# PC1-ISA.net
KiCad netlist of a schematic drawn in EAGLE
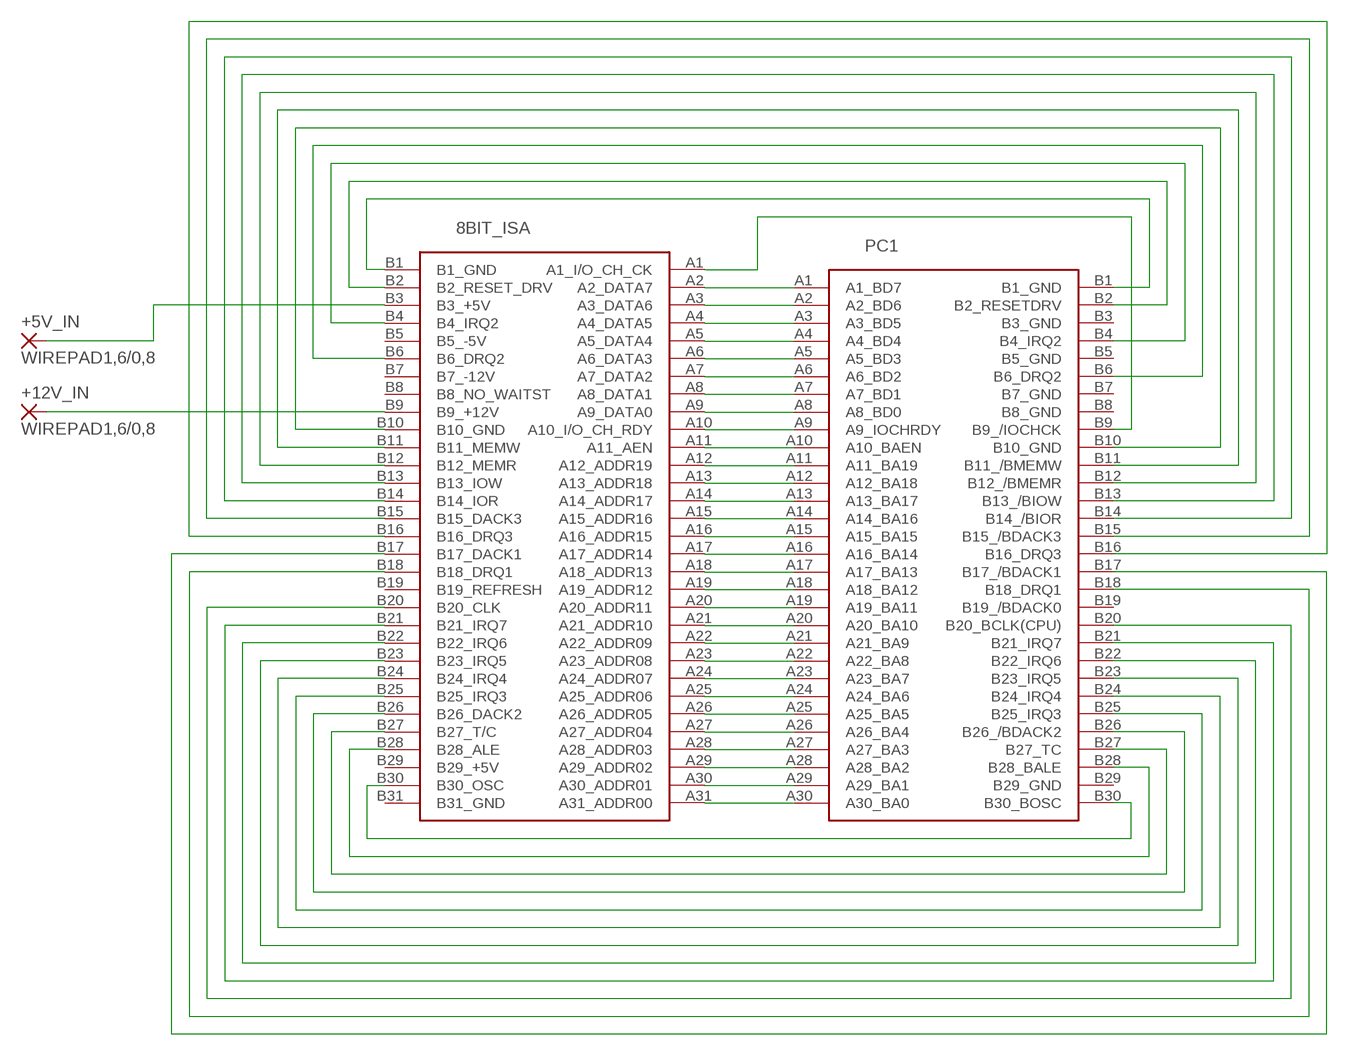
[diagram p0: schematic, sheet 1]

(export (version "E")
  (design (tool "Eeschema 10.0.6"))
  (components
    (comp (ref "+5V_IN")
      (value "WIREPAD1,6/0,8")
      (footprint "eagle-import:1,6_0,8")
      (libsource (lib "eagle-import") (part "WIREPAD1,6/0,8"))
    )
    (comp (ref "+12V_IN")
      (value "WIREPAD1,6/0,8")
      (footprint "eagle-import:1,6_0,8")
      (libsource (lib "eagle-import") (part "WIREPAD1,6/0,8"))
    )
    (comp (ref "8BIT_ISA")
      (value "CARDEDGE_FEMALE_62PINS_8BITISA_STRAIGHT")
      (footprint "eagle-import:CARDEDGE_FEMALE_62PINS_8BITISA_STRAIGHT")
      (libsource (lib "eagle-import") (part "CARDEDGE_FEMALE_62PINS_8BITISA_STRAIGHT"))
    )
    (comp (ref "PC1")
      (value "CARDEDGE_FEMALE_60PINS_PC1_ANGLEDLEFT")
      (footprint "eagle-import:CARDEDGE_FEMALE_60PINS_PC1_ANGLEDLEFT")
      (libsource (lib "eagle-import") (part "CARDEDGE_FEMALE_60PINS_PC1_ANGLEDLEFT"))
    )
  )
  (nets
    (net (code "1") (name "Net-(+5V_IN-P)") (class "Default")
      (node (ref "+5V_IN") (pin "1") (pinfunction "P_1") (pintype "passive"))
      (node (ref "8BIT_ISA") (pin "B3") (pinfunction "B3_+5V_B3") (pintype "bidirectional"))
    )
    (net (code "2") (name "Net-(+12V_IN-P)") (class "Default")
      (node (ref "+12V_IN") (pin "1") (pinfunction "P_1") (pintype "passive"))
      (node (ref "8BIT_ISA") (pin "B9") (pinfunction "B9_+12V_B9") (pintype "bidirectional"))
    )
    (net (code "3") (name "Net-(8BIT_ISA-A1_I{slash}O_CH_CK)") (class "Default")
      (node (ref "8BIT_ISA") (pin "A1") (pinfunction "A1_I/O_CH_CK_A1") (pintype "bidirectional"))
      (node (ref "PC1") (pin "B9") (pinfunction "B9_/IOCHCK_B9") (pintype "bidirectional"))
    )
    (net (code "4") (name "Net-(8BIT_ISA-A2_DATA7)") (class "Default")
      (node (ref "8BIT_ISA") (pin "A2") (pinfunction "A2_DATA7_A2") (pintype "bidirectional"))
      (node (ref "PC1") (pin "A1") (pinfunction "A1_BD7_A1") (pintype "bidirectional"))
    )
    (net (code "5") (name "Net-(8BIT_ISA-A3_DATA6)") (class "Default")
      (node (ref "8BIT_ISA") (pin "A3") (pinfunction "A3_DATA6_A3") (pintype "bidirectional"))
      (node (ref "PC1") (pin "A2") (pinfunction "A2_BD6_A2") (pintype "bidirectional"))
    )
    (net (code "6") (name "Net-(8BIT_ISA-A4_DATA5)") (class "Default")
      (node (ref "8BIT_ISA") (pin "A4") (pinfunction "A4_DATA5_A4") (pintype "bidirectional"))
      (node (ref "PC1") (pin "A3") (pinfunction "A3_BD5_A3") (pintype "bidirectional"))
    )
    (net (code "7") (name "Net-(8BIT_ISA-A5_DATA4)") (class "Default")
      (node (ref "8BIT_ISA") (pin "A5") (pinfunction "A5_DATA4_A5") (pintype "bidirectional"))
      (node (ref "PC1") (pin "A4") (pinfunction "A4_BD4_A4") (pintype "bidirectional"))
    )
    (net (code "8") (name "Net-(8BIT_ISA-A6_DATA3)") (class "Default")
      (node (ref "8BIT_ISA") (pin "A6") (pinfunction "A6_DATA3_A6") (pintype "bidirectional"))
      (node (ref "PC1") (pin "A5") (pinfunction "A5_BD3_A5") (pintype "bidirectional"))
    )
    (net (code "9") (name "Net-(8BIT_ISA-A7_DATA2)") (class "Default")
      (node (ref "8BIT_ISA") (pin "A7") (pinfunction "A7_DATA2_A7") (pintype "bidirectional"))
      (node (ref "PC1") (pin "A6") (pinfunction "A6_BD2_A6") (pintype "bidirectional"))
    )
    (net (code "10") (name "Net-(8BIT_ISA-A8_DATA1)") (class "Default")
      (node (ref "8BIT_ISA") (pin "A8") (pinfunction "A8_DATA1_A8") (pintype "bidirectional"))
      (node (ref "PC1") (pin "A7") (pinfunction "A7_BD1_A7") (pintype "bidirectional"))
    )
    (net (code "11") (name "Net-(8BIT_ISA-A9_DATA0)") (class "Default")
      (node (ref "8BIT_ISA") (pin "A9") (pinfunction "A9_DATA0_A9") (pintype "bidirectional"))
      (node (ref "PC1") (pin "A8") (pinfunction "A8_BD0_A8") (pintype "bidirectional"))
    )
    (net (code "12") (name "Net-(8BIT_ISA-A10_I{slash}O_CH_RDY)") (class "Default")
      (node (ref "8BIT_ISA") (pin "A10") (pinfunction "A10_I/O_CH_RDY_A10") (pintype "bidirectional"))
      (node (ref "PC1") (pin "A9") (pinfunction "A9_IOCHRDY_A9") (pintype "bidirectional"))
    )
    (net (code "13") (name "Net-(8BIT_ISA-A11_AEN)") (class "Default")
      (node (ref "8BIT_ISA") (pin "A11") (pinfunction "A11_AEN_A11") (pintype "bidirectional"))
      (node (ref "PC1") (pin "A10") (pinfunction "A10_BAEN_A10") (pintype "bidirectional"))
    )
    (net (code "14") (name "Net-(8BIT_ISA-A12_ADDR19)") (class "Default")
      (node (ref "8BIT_ISA") (pin "A12") (pinfunction "A12_ADDR19_A12") (pintype "bidirectional"))
      (node (ref "PC1") (pin "A11") (pinfunction "A11_BA19_A11") (pintype "bidirectional"))
    )
    (net (code "15") (name "Net-(8BIT_ISA-A13_ADDR18)") (class "Default")
      (node (ref "8BIT_ISA") (pin "A13") (pinfunction "A13_ADDR18_A13") (pintype "bidirectional"))
      (node (ref "PC1") (pin "A12") (pinfunction "A12_BA18_A12") (pintype "bidirectional"))
    )
    (net (code "16") (name "Net-(8BIT_ISA-A14_ADDR17)") (class "Default")
      (node (ref "8BIT_ISA") (pin "A14") (pinfunction "A14_ADDR17_A14") (pintype "bidirectional"))
      (node (ref "PC1") (pin "A13") (pinfunction "A13_BA17_A13") (pintype "bidirectional"))
    )
    (net (code "17") (name "Net-(8BIT_ISA-A15_ADDR16)") (class "Default")
      (node (ref "8BIT_ISA") (pin "A15") (pinfunction "A15_ADDR16_A15") (pintype "bidirectional"))
      (node (ref "PC1") (pin "A14") (pinfunction "A14_BA16_A14") (pintype "bidirectional"))
    )
    (net (code "18") (name "Net-(8BIT_ISA-A16_ADDR15)") (class "Default")
      (node (ref "8BIT_ISA") (pin "A16") (pinfunction "A16_ADDR15_A16") (pintype "bidirectional"))
      (node (ref "PC1") (pin "A15") (pinfunction "A15_BA15_A15") (pintype "bidirectional"))
    )
    (net (code "19") (name "Net-(8BIT_ISA-A17_ADDR14)") (class "Default")
      (node (ref "8BIT_ISA") (pin "A17") (pinfunction "A17_ADDR14_A17") (pintype "bidirectional"))
      (node (ref "PC1") (pin "A16") (pinfunction "A16_BA14_A16") (pintype "bidirectional"))
    )
    (net (code "20") (name "Net-(8BIT_ISA-A18_ADDR13)") (class "Default")
      (node (ref "8BIT_ISA") (pin "A18") (pinfunction "A18_ADDR13_A18") (pintype "bidirectional"))
      (node (ref "PC1") (pin "A17") (pinfunction "A17_BA13_A17") (pintype "bidirectional"))
    )
    (net (code "21") (name "Net-(8BIT_ISA-A19_ADDR12)") (class "Default")
      (node (ref "8BIT_ISA") (pin "A19") (pinfunction "A19_ADDR12_A19") (pintype "bidirectional"))
      (node (ref "PC1") (pin "A18") (pinfunction "A18_BA12_A18") (pintype "bidirectional"))
    )
    (net (code "22") (name "Net-(8BIT_ISA-A20_ADDR11)") (class "Default")
      (node (ref "8BIT_ISA") (pin "A20") (pinfunction "A20_ADDR11_A20") (pintype "bidirectional"))
      (node (ref "PC1") (pin "A19") (pinfunction "A19_BA11_A19") (pintype "bidirectional"))
    )
    (net (code "23") (name "Net-(8BIT_ISA-A21_ADDR10)") (class "Default")
      (node (ref "8BIT_ISA") (pin "A21") (pinfunction "A21_ADDR10_A21") (pintype "bidirectional"))
      (node (ref "PC1") (pin "A20") (pinfunction "A20_BA10_A20") (pintype "bidirectional"))
    )
    (net (code "24") (name "Net-(8BIT_ISA-A22_ADDR09)") (class "Default")
      (node (ref "8BIT_ISA") (pin "A22") (pinfunction "A22_ADDR09_A22") (pintype "bidirectional"))
      (node (ref "PC1") (pin "A21") (pinfunction "A21_BA9_A21") (pintype "bidirectional"))
    )
    (net (code "25") (name "Net-(8BIT_ISA-A23_ADDR08)") (class "Default")
      (node (ref "8BIT_ISA") (pin "A23") (pinfunction "A23_ADDR08_A23") (pintype "bidirectional"))
      (node (ref "PC1") (pin "A22") (pinfunction "A22_BA8_A22") (pintype "bidirectional"))
    )
    (net (code "26") (name "Net-(8BIT_ISA-A24_ADDR07)") (class "Default")
      (node (ref "8BIT_ISA") (pin "A24") (pinfunction "A24_ADDR07_A24") (pintype "bidirectional"))
      (node (ref "PC1") (pin "A23") (pinfunction "A23_BA7_A23") (pintype "bidirectional"))
    )
    (net (code "27") (name "Net-(8BIT_ISA-A25_ADDR06)") (class "Default")
      (node (ref "8BIT_ISA") (pin "A25") (pinfunction "A25_ADDR06_A25") (pintype "bidirectional"))
      (node (ref "PC1") (pin "A24") (pinfunction "A24_BA6_A24") (pintype "bidirectional"))
    )
    (net (code "28") (name "Net-(8BIT_ISA-A26_ADDR05)") (class "Default")
      (node (ref "8BIT_ISA") (pin "A26") (pinfunction "A26_ADDR05_A26") (pintype "bidirectional"))
      (node (ref "PC1") (pin "A25") (pinfunction "A25_BA5_A25") (pintype "bidirectional"))
    )
    (net (code "29") (name "Net-(8BIT_ISA-A27_ADDR04)") (class "Default")
      (node (ref "8BIT_ISA") (pin "A27") (pinfunction "A27_ADDR04_A27") (pintype "bidirectional"))
      (node (ref "PC1") (pin "A26") (pinfunction "A26_BA4_A26") (pintype "bidirectional"))
    )
    (net (code "30") (name "Net-(8BIT_ISA-A28_ADDR03)") (class "Default")
      (node (ref "8BIT_ISA") (pin "A28") (pinfunction "A28_ADDR03_A28") (pintype "bidirectional"))
      (node (ref "PC1") (pin "A27") (pinfunction "A27_BA3_A27") (pintype "bidirectional"))
    )
    (net (code "31") (name "Net-(8BIT_ISA-A29_ADDR02)") (class "Default")
      (node (ref "8BIT_ISA") (pin "A29") (pinfunction "A29_ADDR02_A29") (pintype "bidirectional"))
      (node (ref "PC1") (pin "A28") (pinfunction "A28_BA2_A28") (pintype "bidirectional"))
    )
    (net (code "32") (name "Net-(8BIT_ISA-A30_ADDR01)") (class "Default")
      (node (ref "8BIT_ISA") (pin "A30") (pinfunction "A30_ADDR01_A30") (pintype "bidirectional"))
      (node (ref "PC1") (pin "A29") (pinfunction "A29_BA1_A29") (pintype "bidirectional"))
    )
    (net (code "33") (name "Net-(8BIT_ISA-A31_ADDR00)") (class "Default")
      (node (ref "8BIT_ISA") (pin "A31") (pinfunction "A31_ADDR00_A31") (pintype "bidirectional"))
      (node (ref "PC1") (pin "A30") (pinfunction "A30_BA0_A30") (pintype "bidirectional"))
    )
    (net (code "34") (name "Net-(8BIT_ISA-B1_GND)") (class "Default")
      (node (ref "8BIT_ISA") (pin "B1") (pinfunction "B1_GND_B1") (pintype "bidirectional"))
      (node (ref "PC1") (pin "B1") (pinfunction "B1_GND_B1") (pintype "bidirectional"))
    )
    (net (code "35") (name "Net-(8BIT_ISA-B2_RESET_DRV)") (class "Default")
      (node (ref "8BIT_ISA") (pin "B2") (pinfunction "B2_RESET_DRV_B2") (pintype "bidirectional"))
      (node (ref "PC1") (pin "B2") (pinfunction "B2_RESETDRV_B2") (pintype "bidirectional"))
    )
    (net (code "36") (name "Net-(8BIT_ISA-B4_IRQ2)") (class "Default")
      (node (ref "8BIT_ISA") (pin "B4") (pinfunction "B4_IRQ2_B4") (pintype "bidirectional"))
      (node (ref "PC1") (pin "B4") (pinfunction "B4_IRQ2_B4") (pintype "bidirectional"))
    )
    (net (code "37") (name "Net-(8BIT_ISA-B6_DRQ2)") (class "Default")
      (node (ref "8BIT_ISA") (pin "B6") (pinfunction "B6_DRQ2_B6") (pintype "bidirectional"))
      (node (ref "PC1") (pin "B6") (pinfunction "B6_DRQ2_B6") (pintype "bidirectional"))
    )
    (net (code "38") (name "Net-(8BIT_ISA-B10_GND)") (class "Default")
      (node (ref "8BIT_ISA") (pin "B10") (pinfunction "B10_GND_B10") (pintype "bidirectional"))
      (node (ref "PC1") (pin "B10") (pinfunction "B10_GND_B10") (pintype "bidirectional"))
    )
    (net (code "39") (name "Net-(8BIT_ISA-B11_MEMW)") (class "Default")
      (node (ref "8BIT_ISA") (pin "B11") (pinfunction "B11_MEMW_B11") (pintype "bidirectional"))
      (node (ref "PC1") (pin "B11") (pinfunction "B11_/BMEMW_B11") (pintype "bidirectional"))
    )
    (net (code "40") (name "Net-(8BIT_ISA-B12_MEMR)") (class "Default")
      (node (ref "8BIT_ISA") (pin "B12") (pinfunction "B12_MEMR_B12") (pintype "bidirectional"))
      (node (ref "PC1") (pin "B12") (pinfunction "B12_/BMEMR_B12") (pintype "bidirectional"))
    )
    (net (code "41") (name "Net-(8BIT_ISA-B13_IOW)") (class "Default")
      (node (ref "8BIT_ISA") (pin "B13") (pinfunction "B13_IOW_B13") (pintype "bidirectional"))
      (node (ref "PC1") (pin "B13") (pinfunction "B13_/BIOW_B13") (pintype "bidirectional"))
    )
    (net (code "42") (name "Net-(8BIT_ISA-B14_IOR)") (class "Default")
      (node (ref "8BIT_ISA") (pin "B14") (pinfunction "B14_IOR_B14") (pintype "bidirectional"))
      (node (ref "PC1") (pin "B14") (pinfunction "B14_/BIOR_B14") (pintype "bidirectional"))
    )
    (net (code "43") (name "Net-(8BIT_ISA-B15_DACK3)") (class "Default")
      (node (ref "8BIT_ISA") (pin "B15") (pinfunction "B15_DACK3_B15") (pintype "bidirectional"))
      (node (ref "PC1") (pin "B15") (pinfunction "B15_/BDACK3_B15") (pintype "bidirectional"))
    )
    (net (code "44") (name "Net-(8BIT_ISA-B16_DRQ3)") (class "Default")
      (node (ref "8BIT_ISA") (pin "B16") (pinfunction "B16_DRQ3_B16") (pintype "bidirectional"))
      (node (ref "PC1") (pin "B16") (pinfunction "B16_DRQ3_B16") (pintype "bidirectional"))
    )
    (net (code "45") (name "Net-(8BIT_ISA-B17_DACK1)") (class "Default")
      (node (ref "8BIT_ISA") (pin "B17") (pinfunction "B17_DACK1_B17") (pintype "bidirectional"))
      (node (ref "PC1") (pin "B17") (pinfunction "B17_/BDACK1_B17") (pintype "bidirectional"))
    )
    (net (code "46") (name "Net-(8BIT_ISA-B18_DRQ1)") (class "Default")
      (node (ref "8BIT_ISA") (pin "B18") (pinfunction "B18_DRQ1_B18") (pintype "bidirectional"))
      (node (ref "PC1") (pin "B18") (pinfunction "B18_DRQ1_B18") (pintype "bidirectional"))
    )
    (net (code "47") (name "Net-(8BIT_ISA-B20_CLK)") (class "Default")
      (node (ref "8BIT_ISA") (pin "B20") (pinfunction "B20_CLK_B20") (pintype "bidirectional"))
      (node (ref "PC1") (pin "B20") (pinfunction "B20_BCLK(CPU)_B20") (pintype "bidirectional"))
    )
    (net (code "48") (name "Net-(8BIT_ISA-B21_IRQ7)") (class "Default")
      (node (ref "8BIT_ISA") (pin "B21") (pinfunction "B21_IRQ7_B21") (pintype "bidirectional"))
      (node (ref "PC1") (pin "B21") (pinfunction "B21_IRQ7_B21") (pintype "bidirectional"))
    )
    (net (code "49") (name "Net-(8BIT_ISA-B22_IRQ6)") (class "Default")
      (node (ref "8BIT_ISA") (pin "B22") (pinfunction "B22_IRQ6_B22") (pintype "bidirectional"))
      (node (ref "PC1") (pin "B22") (pinfunction "B22_IRQ6_B22") (pintype "bidirectional"))
    )
    (net (code "50") (name "Net-(8BIT_ISA-B23_IRQ5)") (class "Default")
      (node (ref "8BIT_ISA") (pin "B23") (pinfunction "B23_IRQ5_B23") (pintype "bidirectional"))
      (node (ref "PC1") (pin "B23") (pinfunction "B23_IRQ5_B23") (pintype "bidirectional"))
    )
    (net (code "51") (name "Net-(8BIT_ISA-B24_IRQ4)") (class "Default")
      (node (ref "8BIT_ISA") (pin "B24") (pinfunction "B24_IRQ4_B24") (pintype "bidirectional"))
      (node (ref "PC1") (pin "B24") (pinfunction "B24_IRQ4_B24") (pintype "bidirectional"))
    )
    (net (code "52") (name "Net-(8BIT_ISA-B25_IRQ3)") (class "Default")
      (node (ref "8BIT_ISA") (pin "B25") (pinfunction "B25_IRQ3_B25") (pintype "bidirectional"))
      (node (ref "PC1") (pin "B25") (pinfunction "B25_IRQ3_B25") (pintype "bidirectional"))
    )
    (net (code "53") (name "Net-(8BIT_ISA-B26_DACK2)") (class "Default")
      (node (ref "8BIT_ISA") (pin "B26") (pinfunction "B26_DACK2_B26") (pintype "bidirectional"))
      (node (ref "PC1") (pin "B26") (pinfunction "B26_/BDACK2_B26") (pintype "bidirectional"))
    )
    (net (code "54") (name "Net-(8BIT_ISA-B27_T{slash}C)") (class "Default")
      (node (ref "8BIT_ISA") (pin "B27") (pinfunction "B27_T/C_B27") (pintype "bidirectional"))
      (node (ref "PC1") (pin "B27") (pinfunction "B27_TC_B27") (pintype "bidirectional"))
    )
    (net (code "55") (name "Net-(8BIT_ISA-B28_ALE)") (class "Default")
      (node (ref "8BIT_ISA") (pin "B28") (pinfunction "B28_ALE_B28") (pintype "bidirectional"))
      (node (ref "PC1") (pin "B28") (pinfunction "B28_BALE_B28") (pintype "bidirectional"))
    )
    (net (code "56") (name "Net-(8BIT_ISA-B30_OSC)") (class "Default")
      (node (ref "8BIT_ISA") (pin "B30") (pinfunction "B30_OSC_B30") (pintype "bidirectional"))
      (node (ref "PC1") (pin "B30") (pinfunction "B30_BOSC_B30") (pintype "bidirectional"))
    )
    (net (code "57") (name "unconnected-(8BIT_ISA-B5_-5V-PadB5)") (class "Default")
      (node (ref "8BIT_ISA") (pin "B5") (pinfunction "B5_-5V_B5") (pintype "bidirectional"))
    )
    (net (code "58") (name "unconnected-(8BIT_ISA-B7_-12V-PadB7)") (class "Default")
      (node (ref "8BIT_ISA") (pin "B7") (pinfunction "B7_-12V_B7") (pintype "bidirectional"))
    )
    (net (code "59") (name "unconnected-(8BIT_ISA-B8_NO_WAITST-PadB8)") (class "Default")
      (node (ref "8BIT_ISA") (pin "B8") (pinfunction "B8_NO_WAITST_B8") (pintype "bidirectional"))
    )
    (net (code "60") (name "unconnected-(8BIT_ISA-B19_REFRESH-PadB19)") (class "Default")
      (node (ref "8BIT_ISA") (pin "B19") (pinfunction "B19_REFRESH_B19") (pintype "bidirectional"))
    )
    (net (code "61") (name "unconnected-(8BIT_ISA-B29_+5V-PadB29)") (class "Default")
      (node (ref "8BIT_ISA") (pin "B29") (pinfunction "B29_+5V_B29") (pintype "bidirectional"))
    )
    (net (code "62") (name "unconnected-(8BIT_ISA-B31_GND-PadB31)") (class "Default")
      (node (ref "8BIT_ISA") (pin "B31") (pinfunction "B31_GND_B31") (pintype "bidirectional"))
    )
    (net (code "63") (name "unconnected-(PC1-B3_GND-PadB3)") (class "Default")
      (node (ref "PC1") (pin "B3") (pinfunction "B3_GND_B3") (pintype "bidirectional"))
    )
    (net (code "64") (name "unconnected-(PC1-B5_GND-PadB5)") (class "Default")
      (node (ref "PC1") (pin "B5") (pinfunction "B5_GND_B5") (pintype "bidirectional"))
    )
    (net (code "65") (name "unconnected-(PC1-B7_GND-PadB7)") (class "Default")
      (node (ref "PC1") (pin "B7") (pinfunction "B7_GND_B7") (pintype "bidirectional"))
    )
    (net (code "66") (name "unconnected-(PC1-B8_GND-PadB8)") (class "Default")
      (node (ref "PC1") (pin "B8") (pinfunction "B8_GND_B8") (pintype "bidirectional"))
    )
    (net (code "67") (name "unconnected-(PC1-B19_{slash}BDACK0-PadB19)") (class "Default")
      (node (ref "PC1") (pin "B19") (pinfunction "B19_/BDACK0_B19") (pintype "bidirectional"))
    )
    (net (code "68") (name "unconnected-(PC1-B29_GND-PadB29)") (class "Default")
      (node (ref "PC1") (pin "B29") (pinfunction "B29_GND_B29") (pintype "bidirectional"))
    )
  )
)
